# EMG_V1A.net
KiCad netlist of a schematic drawn in EAGLE
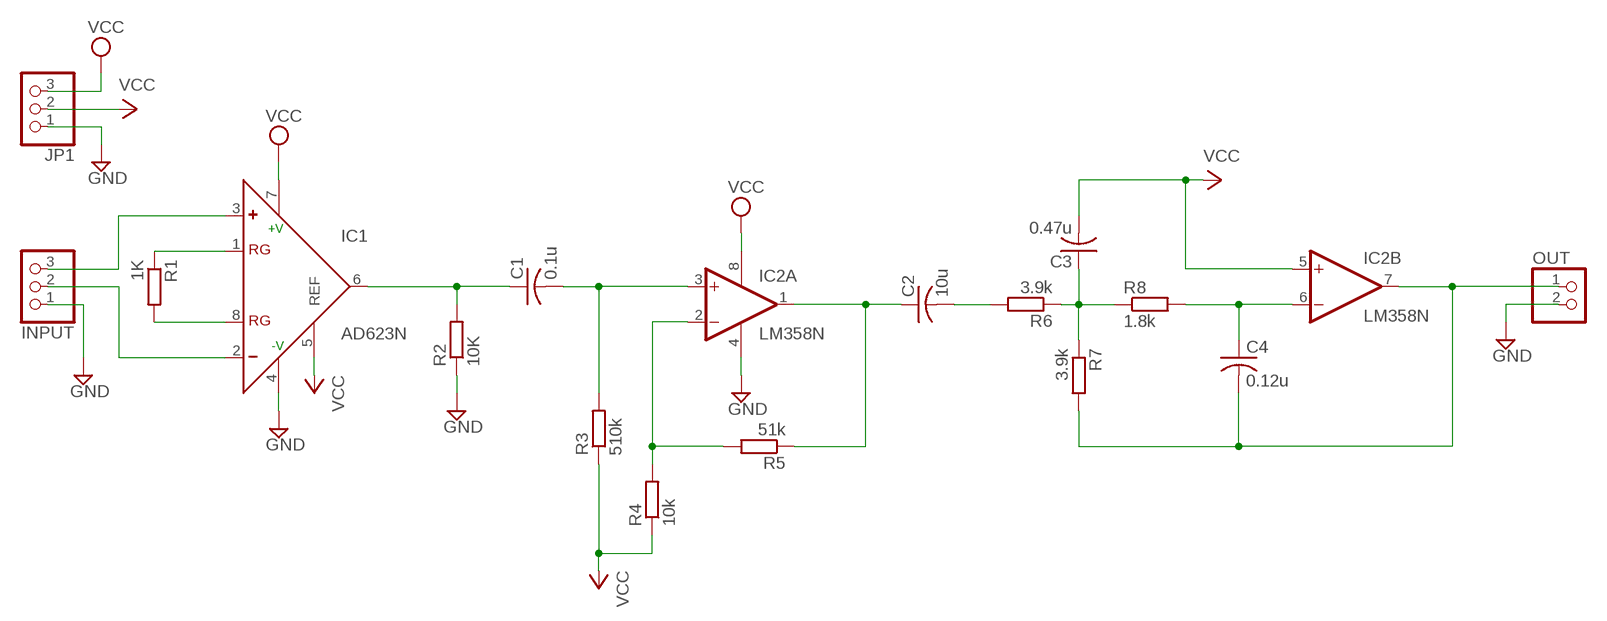
[diagram p0: schematic, sheet 1]

(export (version "E")
  (design (tool "Eeschema 10.0.6"))
  (components
    (comp (ref "C1")
      (value "0.1u")
      (footprint "eagle-import:C050-030X075")
      (libsource (lib "eagle-import") (part "C-US050-030X075"))
    )
    (comp (ref "C2")
      (value "10u")
      (footprint "eagle-import:C050-030X075")
      (libsource (lib "eagle-import") (part "C-US050-030X075"))
    )
    (comp (ref "C3")
      (value "0.47u")
      (footprint "eagle-import:C050-030X075")
      (libsource (lib "eagle-import") (part "C-US050-030X075"))
    )
    (comp (ref "C4")
      (value "0.12u")
      (footprint "eagle-import:C050-030X075")
      (libsource (lib "eagle-import") (part "C-US050-030X075"))
    )
    (comp (ref "IC1")
      (value "AD623N")
      (footprint "eagle-import:DIL08")
      (fields (field (name "MF") "ALTERA CORPORATION") (field (name "MPN") "AD623ANZ"))
      (libsource (lib "eagle-import") (part "AD623N"))
    )
    (comp (ref "IC2")
      (value "LM358N")
      (footprint "eagle-import:DIL08")
      (libsource (lib "eagle-import") (part "LM358N"))
    )
    (comp (ref "INPUT")
      (value "PINHD-1X3")
      (footprint "eagle-import:1X03")
      (libsource (lib "eagle-import") (part "PINHD-1X3"))
    )
    (comp (ref "JP1")
      (value "PINHD-1X3")
      (footprint "eagle-import:1X03")
      (libsource (lib "eagle-import") (part "PINHD-1X3"))
    )
    (comp (ref "OUT")
      (value "PINHD-1X2")
      (footprint "eagle-import:1X02")
      (libsource (lib "eagle-import") (part "PINHD-1X2"))
    )
    (comp (ref "R1")
      (value "1K")
      (footprint "eagle-import:0204_7")
      (libsource (lib "eagle-import") (part "R-EU_0204/7"))
    )
    (comp (ref "R2")
      (value "10K")
      (footprint "eagle-import:0204_7")
      (libsource (lib "eagle-import") (part "R-EU_0204/7"))
    )
    (comp (ref "R3")
      (value "510k")
      (footprint "eagle-import:0204_7")
      (libsource (lib "eagle-import") (part "R-EU_0204/7"))
    )
    (comp (ref "R4")
      (value "10k")
      (footprint "eagle-import:0204_7")
      (libsource (lib "eagle-import") (part "R-EU_0204/7"))
    )
    (comp (ref "R5")
      (value "51k")
      (footprint "eagle-import:0204_7")
      (libsource (lib "eagle-import") (part "R-EU_0204/7"))
    )
    (comp (ref "R6")
      (value "3.9k")
      (footprint "eagle-import:0204_7")
      (libsource (lib "eagle-import") (part "R-EU_0204/7"))
    )
    (comp (ref "R7")
      (value "3.9k")
      (footprint "eagle-import:0204_7")
      (libsource (lib "eagle-import") (part "R-EU_0204/7"))
    )
    (comp (ref "R8")
      (value "1.8k")
      (footprint "eagle-import:0204_7")
      (libsource (lib "eagle-import") (part "R-EU_0204/7"))
    )
  )
  (nets
    (net (code "1") (name "GND") (class "Default")
      (node (ref "IC1") (pin "4") (pinfunction "-V_4") (pintype "power_in"))
      (node (ref "IC2") (pin "4") (pinfunction "V-_4") (pintype "power_in"))
      (node (ref "INPUT") (pin "1") (pinfunction "1_1") (pintype "passive"))
      (node (ref "JP1") (pin "1") (pinfunction "1_1") (pintype "passive"))
      (node (ref "OUT") (pin "2") (pinfunction "2_2") (pintype "passive"))
      (node (ref "R2") (pin "1") (pinfunction "1_1") (pintype "passive"))
    )
    (net (code "2") (name "Net-(C2-Pad2)") (class "Default")
      (node (ref "C2") (pin "2") (pinfunction "2_2") (pintype "passive"))
      (node (ref "R6") (pin "2") (pinfunction "2_2") (pintype "passive"))
    )
    (net (code "3") (name "Net-(C3-Pad1)") (class "Default")
      (node (ref "C3") (pin "1") (pinfunction "1_1") (pintype "passive"))
      (node (ref "R6") (pin "1") (pinfunction "1_1") (pintype "passive"))
      (node (ref "R7") (pin "1") (pinfunction "1_1") (pintype "passive"))
      (node (ref "R8") (pin "1") (pinfunction "1_1") (pintype "passive"))
    )
    (net (code "4") (name "Net-(IC1-+)") (class "Default")
      (node (ref "IC1") (pin "3") (pinfunction "+_3") (pintype "input"))
      (node (ref "INPUT") (pin "3") (pinfunction "3_3") (pintype "passive"))
    )
    (net (code "5") (name "Net-(IC1--)") (class "Default")
      (node (ref "IC1") (pin "2") (pinfunction "-_2") (pintype "input"))
      (node (ref "INPUT") (pin "2") (pinfunction "2_2") (pintype "passive"))
    )
    (net (code "6") (name "Net-(IC1-OUT)") (class "Default")
      (node (ref "C1") (pin "1") (pinfunction "1_1") (pintype "passive"))
      (node (ref "IC1") (pin "6") (pinfunction "OUT_6") (pintype "output"))
      (node (ref "R2") (pin "2") (pinfunction "2_2") (pintype "passive"))
    )
    (net (code "7") (name "Net-(IC1-RG-Pad1)") (class "Default")
      (node (ref "IC1") (pin "1") (pinfunction "RG_1") (pintype "passive"))
      (node (ref "R1") (pin "1") (pinfunction "1_1") (pintype "passive"))
    )
    (net (code "8") (name "Net-(IC1-RG-Pad8)") (class "Default")
      (node (ref "IC1") (pin "8") (pinfunction "RG_8") (pintype "passive"))
      (node (ref "R1") (pin "2") (pinfunction "2_2") (pintype "passive"))
    )
    (net (code "9") (name "Net-(IC2A-+IN)") (class "Default")
      (node (ref "C1") (pin "2") (pinfunction "2_2") (pintype "passive"))
      (node (ref "IC2") (pin "3") (pinfunction "+IN_3") (pintype "input"))
      (node (ref "R3") (pin "2") (pinfunction "2_2") (pintype "passive"))
    )
    (net (code "10") (name "Net-(IC2A--IN)") (class "Default")
      (node (ref "IC2") (pin "2") (pinfunction "-IN_2") (pintype "input"))
      (node (ref "R4") (pin "2") (pinfunction "2_2") (pintype "passive"))
      (node (ref "R5") (pin "2") (pinfunction "2_2") (pintype "passive"))
    )
    (net (code "11") (name "Net-(IC2A-OUT)") (class "Default")
      (node (ref "C2") (pin "1") (pinfunction "1_1") (pintype "passive"))
      (node (ref "IC2") (pin "1") (pinfunction "OUT_1") (pintype "output"))
      (node (ref "R5") (pin "1") (pinfunction "1_1") (pintype "passive"))
    )
    (net (code "12") (name "Net-(IC2B--IN)") (class "Default")
      (node (ref "C4") (pin "1") (pinfunction "1_1") (pintype "passive"))
      (node (ref "IC2") (pin "6") (pinfunction "-IN_6") (pintype "input"))
      (node (ref "R8") (pin "2") (pinfunction "2_2") (pintype "passive"))
    )
    (net (code "13") (name "Net-(IC2B-OUT)") (class "Default")
      (node (ref "C4") (pin "2") (pinfunction "2_2") (pintype "passive"))
      (node (ref "IC2") (pin "7") (pinfunction "OUT_7") (pintype "output"))
      (node (ref "OUT") (pin "1") (pinfunction "1_1") (pintype "passive"))
      (node (ref "R7") (pin "2") (pinfunction "2_2") (pintype "passive"))
    )
    (net (code "14") (name "VCC") (class "Default")
      (node (ref "C3") (pin "2") (pinfunction "2_2") (pintype "passive"))
      (node (ref "IC1") (pin "5") (pinfunction "REF_5") (pintype "passive"))
      (node (ref "IC1") (pin "7") (pinfunction "+V_7") (pintype "power_in"))
      (node (ref "IC2") (pin "5") (pinfunction "+IN_5") (pintype "input"))
      (node (ref "IC2") (pin "8") (pinfunction "V+_8") (pintype "power_in"))
      (node (ref "JP1") (pin "2") (pinfunction "2_2") (pintype "passive"))
      (node (ref "JP1") (pin "3") (pinfunction "3_3") (pintype "passive"))
      (node (ref "R3") (pin "1") (pinfunction "1_1") (pintype "passive"))
      (node (ref "R4") (pin "1") (pinfunction "1_1") (pintype "passive"))
    )
  )
)
